# untitled.net
KiCad netlist of a schematic drawn in EAGLE
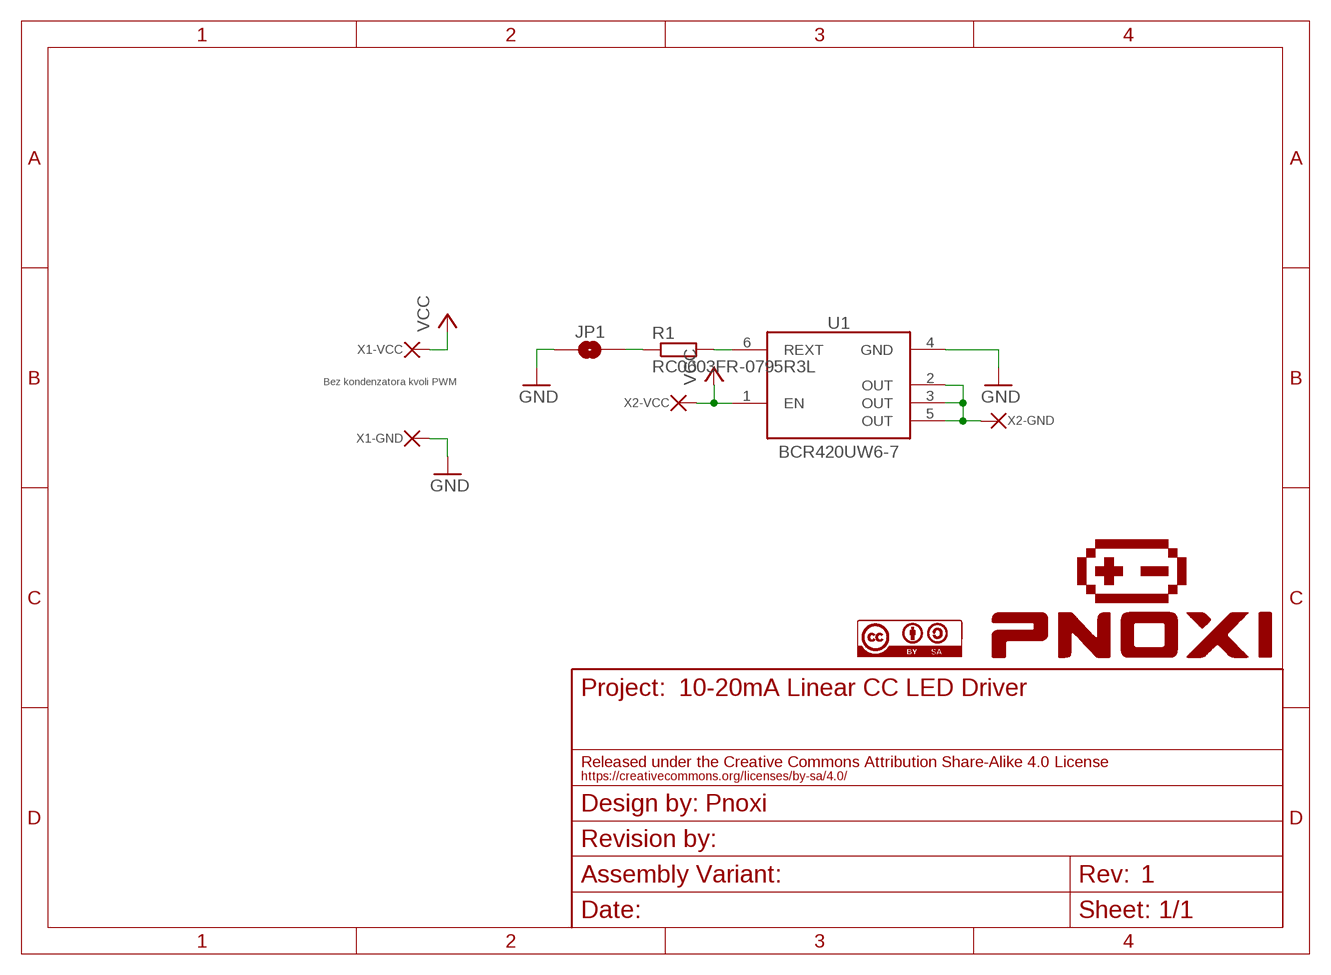
[diagram p0: schematic, sheet 1]

(export (version "E")
  (design (tool "Eeschema 10.0.6"))
  (components
    (comp (ref "JP1")
      (value "SMD-JUMPER-2-NO")
      (footprint "eagle-import:SMD-JUMPER-2-NO")
      (libsource (lib "eagle-import") (part "SMD-JUMPER-2-NO"))
    )
    (comp (ref "R1")
      (value "RC0603FR-0795R3L")
      (footprint "eagle-import:0603")
      (libsource (lib "eagle-import") (part "R_EU_0603"))
    )
    (comp (ref "U1")
      (value "BCR420UW6-7")
      (footprint "eagle-import:SOP95P250X110-6N-1_NO_THERMALS")
      (libsource (lib "eagle-import") (part "BCR420U_NO_THERMALS"))
    )
    (comp (ref "X1")
      (value "SMD_PAD2")
      (footprint "eagle-import:SMD_PAD_2")
      (libsource (lib "eagle-import") (part "SMD_PAD2"))
    )
    (comp (ref "X2")
      (value "SMD_PAD2")
      (footprint "eagle-import:SMD_PAD_2")
      (libsource (lib "eagle-import") (part "SMD_PAD2"))
    )
  )
  (nets
    (net (code "1") (name "GND") (class "Default")
      (node (ref "JP1") (pin "P$1") (pinfunction "1_P$1") (pintype "passive"))
      (node (ref "U1") (pin "4") (pinfunction "GND_4") (pintype "power_in"))
      (node (ref "X1") (pin "GND") (pinfunction "P_GND") (pintype "passive"))
      (node (ref "X1") (pin "GND1") (pinfunction "P_GND1") (pintype "passive"))
      (node (ref "X1") (pin "GND2") (pinfunction "P_GND2") (pintype "passive"))
      (node (ref "X1") (pin "GND3") (pinfunction "P_GND3") (pintype "passive"))
    )
    (net (code "2") (name "Net-(JP1-2)") (class "Default")
      (node (ref "JP1") (pin "P$2") (pinfunction "2_P$2") (pintype "passive"))
      (node (ref "R1") (pin "1") (pinfunction "1_1") (pintype "passive"))
    )
    (net (code "3") (name "Net-(U1-OUT-Pad2)") (class "Default")
      (node (ref "U1") (pin "2") (pinfunction "OUT_2") (pintype "output"))
      (node (ref "U1") (pin "3") (pinfunction "OUT_3") (pintype "output"))
      (node (ref "U1") (pin "5") (pinfunction "OUT_5") (pintype "output"))
      (node (ref "X2") (pin "GND") (pinfunction "P_GND") (pintype "passive"))
      (node (ref "X2") (pin "GND1") (pinfunction "P_GND1") (pintype "passive"))
      (node (ref "X2") (pin "GND2") (pinfunction "P_GND2") (pintype "passive"))
      (node (ref "X2") (pin "GND3") (pinfunction "P_GND3") (pintype "passive"))
    )
    (net (code "4") (name "Net-(U1-REXT)") (class "Default")
      (node (ref "R1") (pin "2") (pinfunction "2_2") (pintype "passive"))
      (node (ref "U1") (pin "6") (pinfunction "REXT_6") (pintype "passive"))
    )
    (net (code "5") (name "VCC") (class "Default")
      (node (ref "U1") (pin "1") (pinfunction "EN_1") (pintype "input"))
      (node (ref "X1") (pin "VCC") (pinfunction "P_VCC") (pintype "passive"))
      (node (ref "X1") (pin "VCC1") (pinfunction "P_VCC1") (pintype "passive"))
      (node (ref "X1") (pin "VCC2") (pinfunction "P_VCC2") (pintype "passive"))
      (node (ref "X1") (pin "VCC3") (pinfunction "P_VCC3") (pintype "passive"))
      (node (ref "X2") (pin "VCC") (pinfunction "P_VCC") (pintype "passive"))
      (node (ref "X2") (pin "VCC1") (pinfunction "P_VCC1") (pintype "passive"))
      (node (ref "X2") (pin "VCC2") (pinfunction "P_VCC2") (pintype "passive"))
      (node (ref "X2") (pin "VCC3") (pinfunction "P_VCC3") (pintype "passive"))
    )
  )
)
